# power.net
KiCad netlist of a schematic drawn in Altium Designer
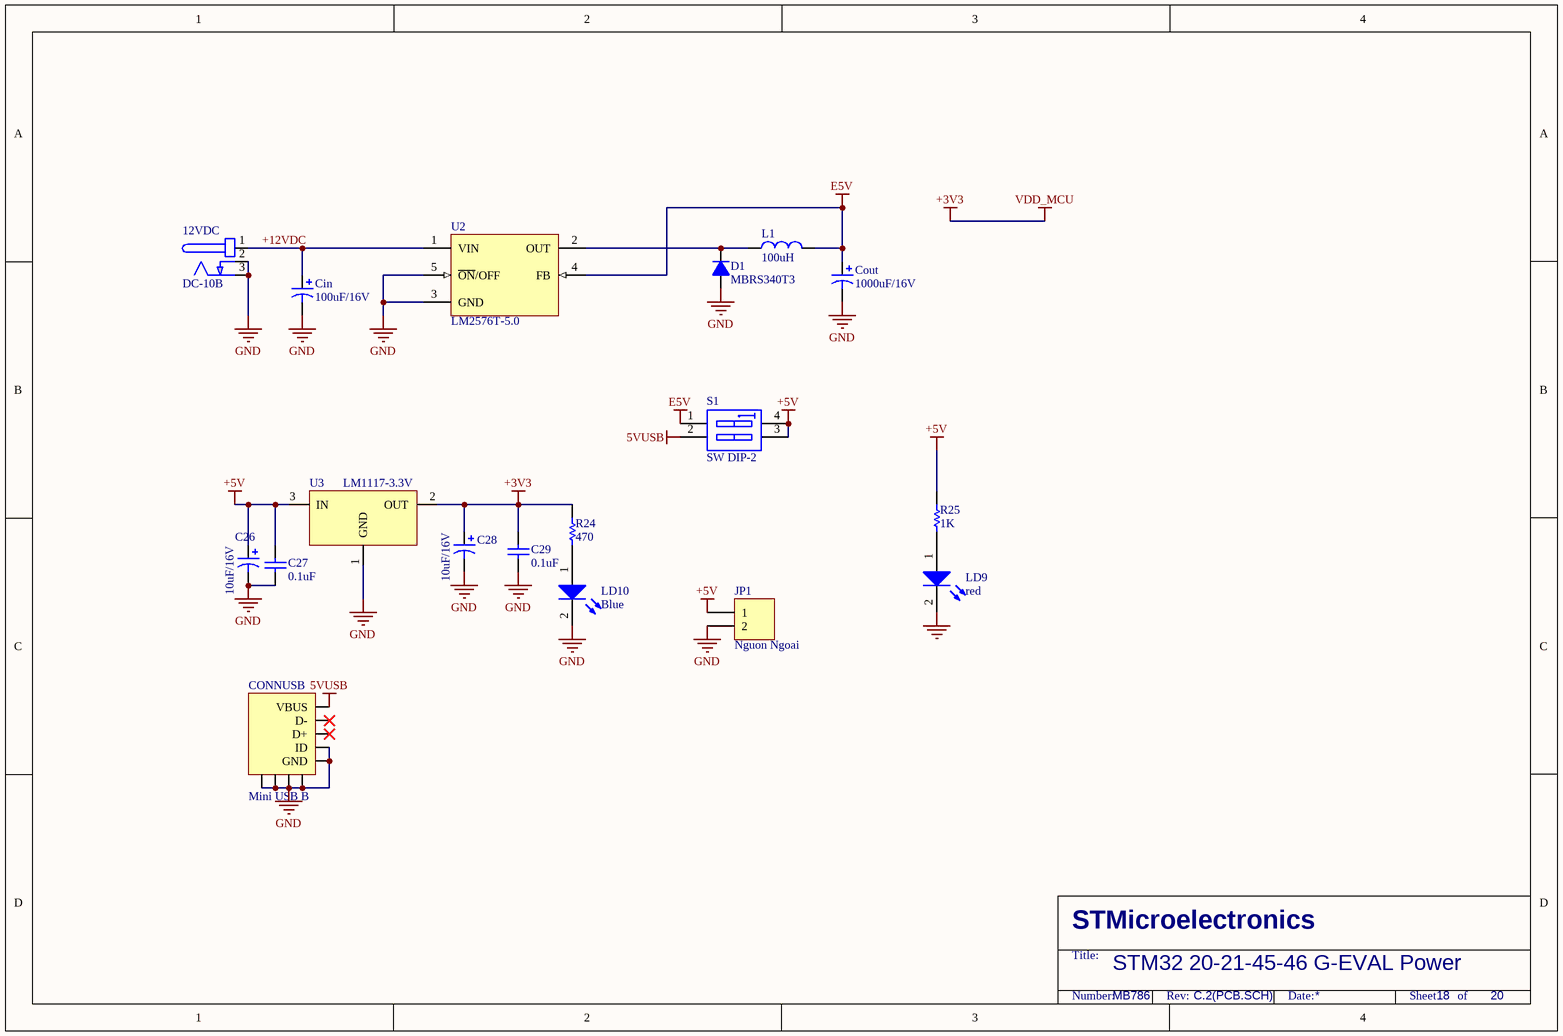
[diagram p0: power.SchDoc]

(export (version "E")
  (design (tool "Eeschema 10.0.6"))
  (components
    (comp (ref "12VDC")
      (value "DC-10B")
      (footprint "DC IN")
      (libsource (lib "STR910_SCHLIB") (part "PJ202A"))
    )
    (comp (ref "C26")
      (value "10uF/16V")
      (footprint "AVX-CAPC3528_V")
      (description "Tu Hoa")
      (libsource (lib "AVX-CAP-P-2") (part "AVX-CAP-P-2"))
    )
    (comp (ref "C27")
      (value "0.1uF")
      (footprint "0603_C")
      (description "Capacitor")
      (fields (field (name "PUBLISHER") "Altium Limited"))
      (libsource (lib "Miscellaneous Devices") (part "Cap"))
    )
    (comp (ref "C28")
      (value "10uF/16V")
      (footprint "AVX-CAPC3528_V")
      (description "Tu hoa")
      (libsource (lib "AVX-CAP-P-2") (part "AVX-CAP-P-2"))
    )
    (comp (ref "C29")
      (value "0.1uF")
      (footprint "0603_C")
      (description "Capacitor")
      (fields (field (name "PUBLISHER") "Altium Limited"))
      (libsource (lib "Miscellaneous Devices") (part "Cap"))
    )
    (comp (ref "Cin")
      (value "100uF/16V")
      (footprint "CAPAE660X540N")
      (description "Tu hoa")
      (libsource (lib "AVX-CAP-P-2") (part "AVX-CAP-P-2"))
    )
    (comp (ref "CONNUSB")
      (value "Mini USB B")
      (footprint "USB MINI B RECEPTACLE")
      (description "FCI Mini USB B Recptacle Right Angle")
      (libsource (lib "connector") (part "10033526-N3212LF"))
    )
    (comp (ref "Cout")
      (value "1000uF/16V")
      (footprint "CAPAE1030X1020N")
      (description "Tu hoa")
      (libsource (lib "AVX-CAP-P-2") (part "AVX-CAP-P-2"))
    )
    (comp (ref "D1")
      (value "MBRS340T3")
      (footprint "DO-214AB")
      (description "Diode 1A")
      (libsource (lib "Cty1") (part "D1A"))
    )
    (comp (ref "JP1")
      (value "Nguon Ngoai")
      (footprint "HDR1X2")
      (description "Header, 2-Pin")
      (fields (field (name "PUBLISHER") "Altium Limited"))
      (libsource (lib "Miscellaneous Connectors") (part "Header 2"))
    )
    (comp (ref "L1")
      (value "100uH")
      (footprint "IND_BOURNS_PM127SH")
      (description "Inductor")
      (libsource (lib "Cty1") (part "L1"))
    )
    (comp (ref "LD9")
      (value "red")
      (footprint "0805_LED")
      (description "Typical RED, GREEN, YELLOW, AMBER GaAs LED")
      (fields (field (name "PUBLISHER") "Altium Limited"))
      (libsource (lib "Miscellaneous Devices") (part "LED2"))
    )
    (comp (ref "LD10")
      (value "Blue")
      (footprint "0805_LED")
      (description "Typical RED, GREEN, YELLOW, AMBER GaAs LED")
      (fields (field (name "PUBLISHER") "Altium Limited"))
      (libsource (lib "Miscellaneous Devices") (part "LED2"))
    )
    (comp (ref "R24")
      (value "470")
      (footprint "0603_R")
      (description "Resistor")
      (fields (field (name "PUBLISHER") "Altium Limited"))
      (libsource (lib "Miscellaneous Devices") (part "res1"))
    )
    (comp (ref "R25")
      (value "1K")
      (footprint "0603_R")
      (description "Resistor")
      (fields (field (name "PUBLISHER") "Altium Limited"))
      (libsource (lib "Miscellaneous Devices") (part "res1"))
    )
    (comp (ref "S1")
      (value "SW DIP-2")
      (footprint "SW_OMRON_A6S-2102-H")
      (description "DIP Switch, 2 Position, SPST")
      (fields (field (name "PUBLISHER") "Altium Limited"))
      (libsource (lib "Miscellaneous Devices") (part "SW DIP-2"))
    )
    (comp (ref "U2")
      (value "LM2576T-5.0")
      (footprint "TO263-5")
      (description "SIMPLE SWITCHER; 3A Step-Down Voltage Regulator")
      (fields
        (field (name "MANUFACTURER") "National Semiconductor")
        (field (name "DIGIKEYPARTNUMBER") "LM2576T-5.0-ND")
        (field (name "PUBLISHER") "Altium Limited")
      )
      (libsource (lib "Cty1") (part "LM2576T-5.0"))
    )
    (comp (ref "U3")
      (value "LM1117-3.3V")
      (footprint "SOT223-4N")
      (description "800mA Low-Dropout Linear Regulator")
      (fields (field (name "CREATOR") "Nguyen Ba Bien"))
      (libsource (lib "Cty1") (part "LM1117"))
    )
  )
  (nets
    (net (code "1") (name "+3V3") (class "Default")
      (node (ref "C28") (pin "1") (pinfunction "1_1") (pintype "passive"))
      (node (ref "C29") (pin "1") (pinfunction "1_1") (pintype "passive"))
      (node (ref "R24") (pin "2") (pinfunction "2_2") (pintype "passive"))
      (node (ref "U3") (pin "2") (pinfunction "OUT_2") (pintype "passive"))
    )
    (net (code "2") (name "+5V") (class "Default")
      (node (ref "C26") (pin "1") (pinfunction "1_1") (pintype "passive"))
      (node (ref "C27") (pin "1") (pinfunction "1_1") (pintype "passive"))
      (node (ref "JP1") (pin "1") (pinfunction "1_1") (pintype "passive"))
      (node (ref "R25") (pin "2") (pinfunction "2_2") (pintype "passive"))
      (node (ref "S1") (pin "3") (pinfunction "B2_3") (pintype "passive"))
      (node (ref "S1") (pin "4") (pinfunction "B1_4") (pintype "passive"))
      (node (ref "U3") (pin "3") (pinfunction "IN_3") (pintype "passive"))
    )
    (net (code "3") (name "/+12VDC") (class "Default")
      (node (ref "12VDC") (pin "1") (pinfunction "+_1") (pintype "passive"))
      (node (ref "Cin") (pin "1") (pinfunction "1_1") (pintype "passive"))
      (node (ref "U2") (pin "1") (pinfunction "VIN_1") (pintype "power_in"))
    )
    (net (code "4") (name "5VUSB") (class "Default")
      (node (ref "CONNUSB") (pin "1") (pinfunction "VBUS_1") (pintype "passive"))
      (node (ref "S1") (pin "2") (pinfunction "A2_2") (pintype "passive"))
    )
    (net (code "5") (name "E5V") (class "Default")
      (node (ref "Cout") (pin "1") (pinfunction "1_1") (pintype "passive"))
      (node (ref "L1") (pin "2") (pinfunction "2_2") (pintype "passive"))
      (node (ref "S1") (pin "1") (pinfunction "A1_1") (pintype "passive"))
      (node (ref "U2") (pin "4") (pinfunction "FB_4") (pintype "input"))
    )
    (net (code "6") (name "GND") (class "Default")
      (node (ref "12VDC") (pin "2") (pinfunction "GND_2") (pintype "passive"))
      (node (ref "12VDC") (pin "3") (pinfunction "GND_3") (pintype "passive"))
      (node (ref "C26") (pin "2") (pinfunction "2_2") (pintype "passive"))
      (node (ref "C27") (pin "2") (pinfunction "2_2") (pintype "passive"))
      (node (ref "C28") (pin "2") (pinfunction "2_2") (pintype "passive"))
      (node (ref "C29") (pin "2") (pinfunction "2_2") (pintype "passive"))
      (node (ref "CONNUSB") (pin "4") (pinfunction "ID_4") (pintype "passive"))
      (node (ref "CONNUSB") (pin "5") (pinfunction "GND_5") (pintype "passive"))
      (node (ref "CONNUSB") (pin "SHIELD") (pintype "passive"))
      (node (ref "Cin") (pin "2") (pinfunction "2_2") (pintype "passive"))
      (node (ref "Cout") (pin "2") (pinfunction "2_2") (pintype "passive"))
      (node (ref "D1") (pin "1") (pinfunction "A_1") (pintype "passive"))
      (node (ref "JP1") (pin "2") (pinfunction "2_2") (pintype "passive"))
      (node (ref "LD10") (pin "2") (pinfunction "K_2") (pintype "passive"))
      (node (ref "LD9") (pin "2") (pinfunction "K_2") (pintype "passive"))
      (node (ref "U2") (pin "3") (pinfunction "GND_3") (pintype "power_in"))
      (node (ref "U2") (pin "5") (pinfunction "~{ON}/OFF_5") (pintype "input"))
      (node (ref "U3") (pin "1") (pinfunction "GND_1") (pintype "passive"))
    )
    (net (code "7") (name "Net-(D1-K)") (class "Default")
      (node (ref "D1") (pin "2") (pinfunction "K_2") (pintype "passive"))
      (node (ref "L1") (pin "1") (pinfunction "1_1") (pintype "passive"))
      (node (ref "U2") (pin "2") (pinfunction "OUT_2") (pintype "power_in"))
    )
    (net (code "8") (name "Net-(LD9-A)") (class "Default")
      (node (ref "LD9") (pin "1") (pinfunction "A_1") (pintype "passive"))
      (node (ref "R25") (pin "1") (pinfunction "1_1") (pintype "passive"))
    )
    (net (code "9") (name "Net-(LD10-A)") (class "Default")
      (node (ref "LD10") (pin "1") (pinfunction "A_1") (pintype "passive"))
      (node (ref "R24") (pin "1") (pinfunction "1_1") (pintype "passive"))
    )
    (net (code "10") (name "unconnected-(CONNUSB-D+-Pad3)") (class "Default")
      (node (ref "CONNUSB") (pin "3") (pinfunction "D+_3") (pintype "passive+no_connect"))
    )
    (net (code "11") (name "unconnected-(CONNUSB-D--Pad2)") (class "Default")
      (node (ref "CONNUSB") (pin "2") (pinfunction "D-_2") (pintype "passive+no_connect"))
    )
  )
)
